# M8357pld.net
KiCad netlist of a schematic drawn in EAGLE
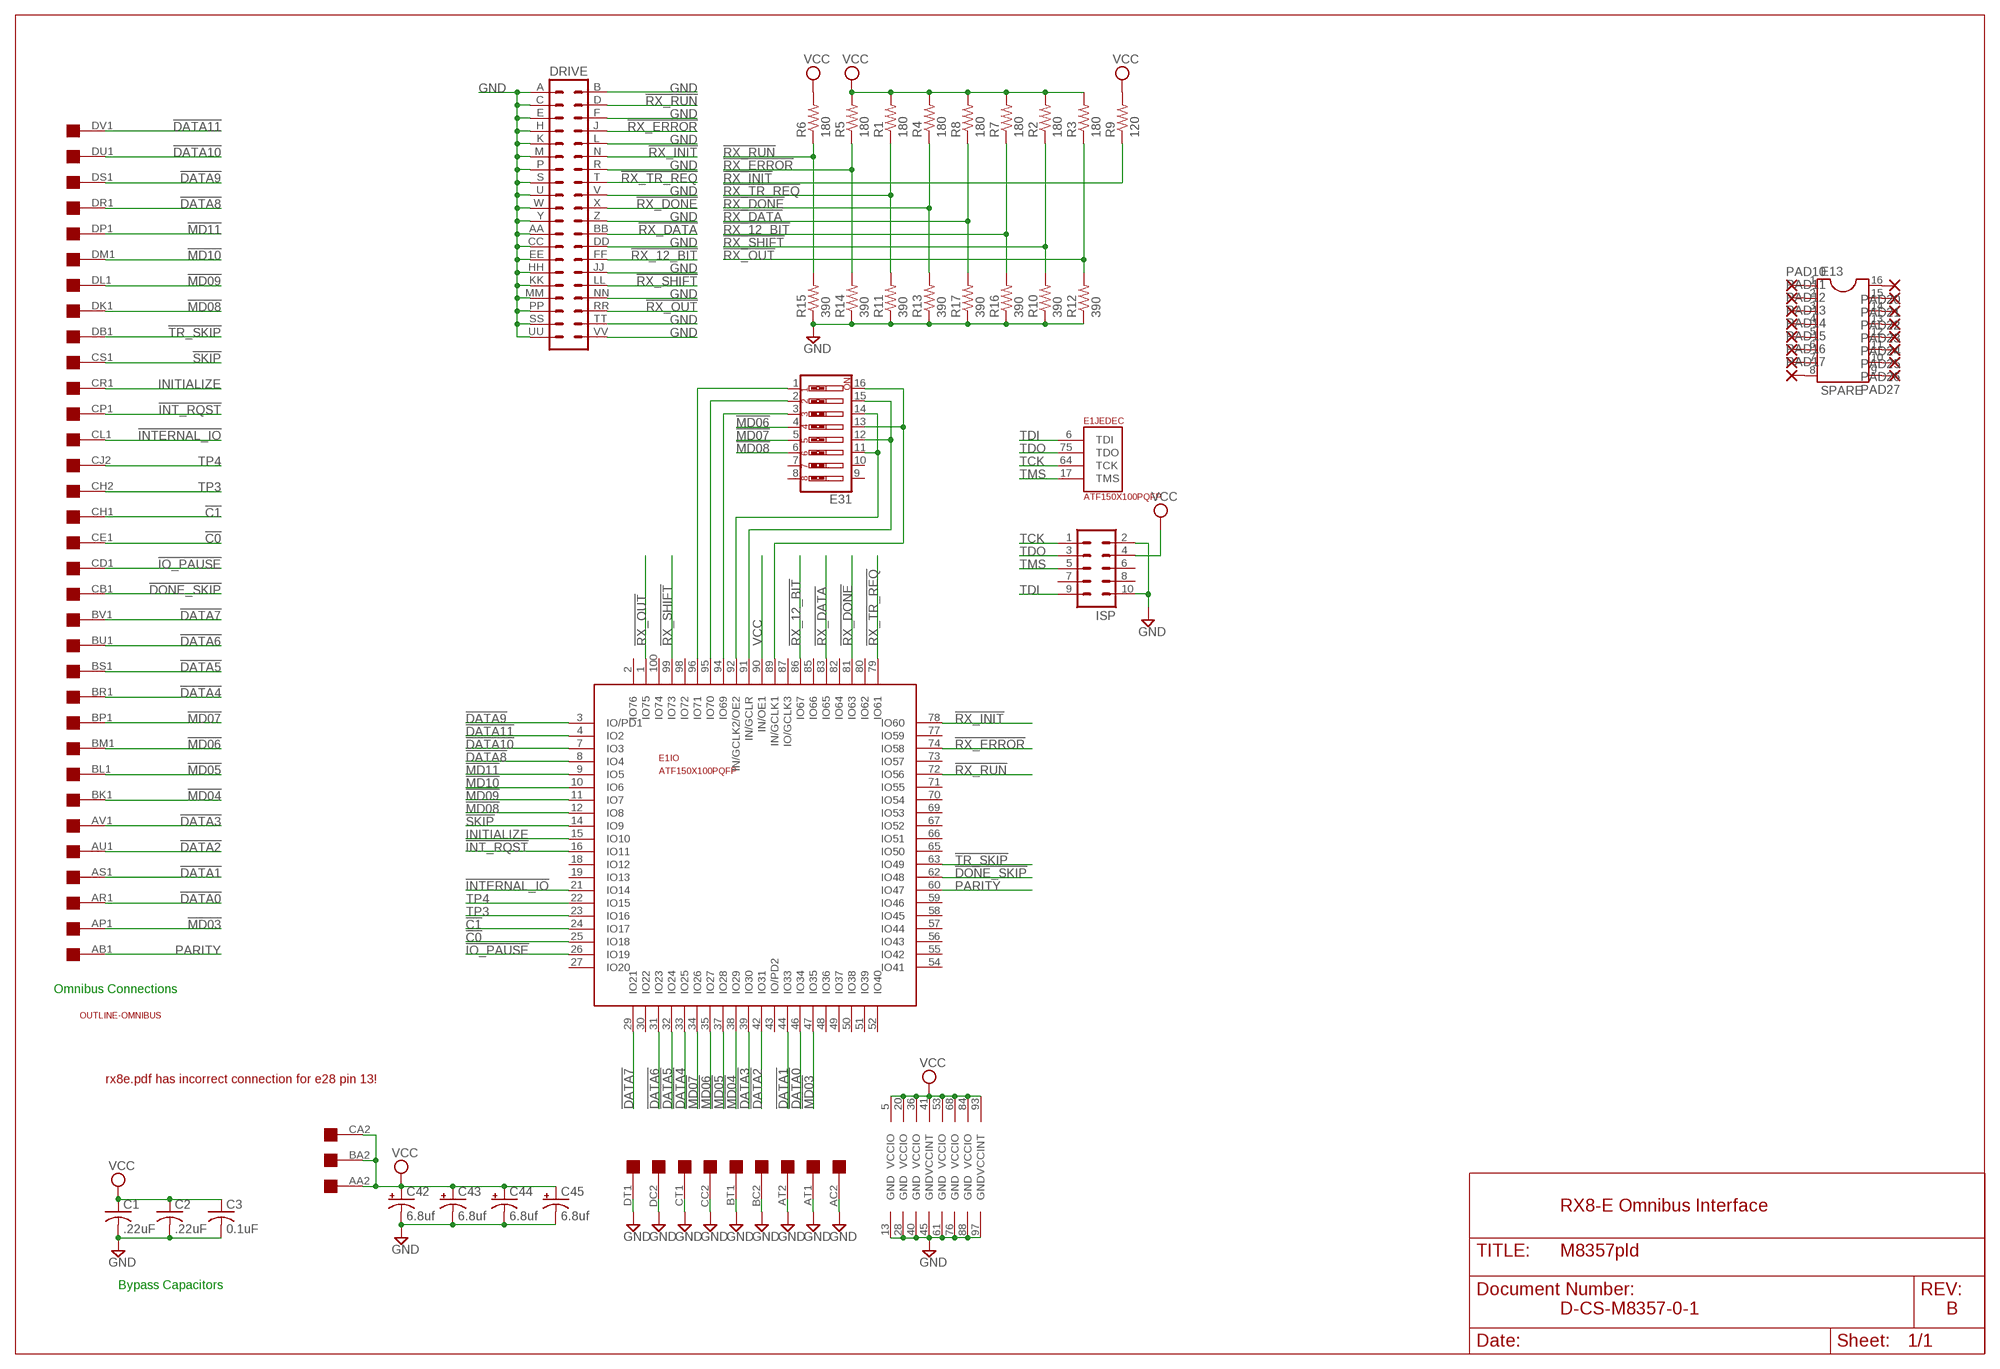
[diagram p0: schematic, sheet 1]

(export (version "E")
  (design (tool "Eeschema 10.0.6"))
  (components
    (comp (ref "C1")
      (value ".22uF")
      (footprint "eagle-import:C050-025X075")
      (libsource (lib "eagle-import") (part "C-US050-025X075"))
    )
    (comp (ref "C2")
      (value ".22uF")
      (footprint "eagle-import:C050-025X075")
      (libsource (lib "eagle-import") (part "C-US050-025X075"))
    )
    (comp (ref "C3")
      (value "0.1uF")
      (footprint "eagle-import:C050-025X075")
      (libsource (lib "eagle-import") (part "C-US050-025X075"))
    )
    (comp (ref "C42")
      (value "6.8uf")
      (footprint "eagle-import:E22-6")
      (libsource (lib "eagle-import") (part "CPOL-USE22-6AXIAL"))
    )
    (comp (ref "C43")
      (value "6.8uf")
      (footprint "eagle-import:E22-6")
      (libsource (lib "eagle-import") (part "CPOL-USE22-6AXIAL"))
    )
    (comp (ref "C44")
      (value "6.8uf")
      (footprint "eagle-import:E22-6")
      (libsource (lib "eagle-import") (part "CPOL-USE22-6AXIAL"))
    )
    (comp (ref "C45")
      (value "6.8uf")
      (footprint "eagle-import:E22-6")
      (libsource (lib "eagle-import") (part "CPOL-USE22-6AXIAL"))
    )
    (comp (ref "DRIVE")
      (value "DEC40PINH")
      (footprint "eagle-import:DEC40PINH")
      (libsource (lib "eagle-import") (part "DEC40PINH"))
    )
    (comp (ref "E1")
      (value "ATF150X100PQFP")
      (footprint "eagle-import:PQFP-100")
      (libsource (lib "eagle-import") (part "ATF150X100PQFP"))
    )
    (comp (ref "E13")
      (value "SPARE")
      (footprint "eagle-import:DIL16")
      (libsource (lib "eagle-import") (part "DIL16"))
    )
    (comp (ref "E31")
      (value "SW_DIP-8")
      (footprint "eagle-import:EDG-08")
      (libsource (lib "eagle-import") (part "SW_DIP-8"))
    )
    (comp (ref "ISP")
      (value "ML10")
      (footprint "eagle-import:ML10")
      (libsource (lib "eagle-import") (part "ML10"))
    )
    (comp (ref "PAD10")
      (value "1,6/0,8")
      (footprint "eagle-import:1,6_0,8")
      (libsource (lib "eagle-import") (part "1,6/0,8"))
    )
    (comp (ref "PAD11")
      (value "1,6/0,8")
      (footprint "eagle-import:1,6_0,8")
      (libsource (lib "eagle-import") (part "1,6/0,8"))
    )
    (comp (ref "PAD12")
      (value "1,6/0,8")
      (footprint "eagle-import:1,6_0,8")
      (libsource (lib "eagle-import") (part "1,6/0,8"))
    )
    (comp (ref "PAD13")
      (value "1,6/0,8")
      (footprint "eagle-import:1,6_0,8")
      (libsource (lib "eagle-import") (part "1,6/0,8"))
    )
    (comp (ref "PAD14")
      (value "1,6/0,8")
      (footprint "eagle-import:1,6_0,8")
      (libsource (lib "eagle-import") (part "1,6/0,8"))
    )
    (comp (ref "PAD15")
      (value "1,6/0,8")
      (footprint "eagle-import:1,6_0,8")
      (libsource (lib "eagle-import") (part "1,6/0,8"))
    )
    (comp (ref "PAD16")
      (value "1,6/0,8")
      (footprint "eagle-import:1,6_0,8")
      (libsource (lib "eagle-import") (part "1,6/0,8"))
    )
    (comp (ref "PAD17")
      (value "1,6/0,8")
      (footprint "eagle-import:1,6_0,8")
      (libsource (lib "eagle-import") (part "1,6/0,8"))
    )
    (comp (ref "PAD20")
      (value "1,6/0,8")
      (footprint "eagle-import:1,6_0,8")
      (libsource (lib "eagle-import") (part "1,6/0,8"))
    )
    (comp (ref "PAD21")
      (value "1,6/0,8")
      (footprint "eagle-import:1,6_0,8")
      (libsource (lib "eagle-import") (part "1,6/0,8"))
    )
    (comp (ref "PAD22")
      (value "1,6/0,8")
      (footprint "eagle-import:1,6_0,8")
      (libsource (lib "eagle-import") (part "1,6/0,8"))
    )
    (comp (ref "PAD23")
      (value "1,6/0,8")
      (footprint "eagle-import:1,6_0,8")
      (libsource (lib "eagle-import") (part "1,6/0,8"))
    )
    (comp (ref "PAD24")
      (value "1,6/0,8")
      (footprint "eagle-import:1,6_0,8")
      (libsource (lib "eagle-import") (part "1,6/0,8"))
    )
    (comp (ref "PAD25")
      (value "1,6/0,8")
      (footprint "eagle-import:1,6_0,8")
      (libsource (lib "eagle-import") (part "1,6/0,8"))
    )
    (comp (ref "PAD26")
      (value "1,6/0,8")
      (footprint "eagle-import:1,6_0,8")
      (libsource (lib "eagle-import") (part "1,6/0,8"))
    )
    (comp (ref "PAD27")
      (value "1,6/0,8")
      (footprint "eagle-import:1,6_0,8")
      (libsource (lib "eagle-import") (part "1,6/0,8"))
    )
    (comp (ref "R1")
      (value "180")
      (footprint "eagle-import:0207_10")
      (libsource (lib "eagle-import") (part "R-US_0207/10"))
    )
    (comp (ref "R2")
      (value "180")
      (footprint "eagle-import:0207_10")
      (libsource (lib "eagle-import") (part "R-US_0207/10"))
    )
    (comp (ref "R3")
      (value "180")
      (footprint "eagle-import:0207_10")
      (libsource (lib "eagle-import") (part "R-US_0207/10"))
    )
    (comp (ref "R4")
      (value "180")
      (footprint "eagle-import:0207_10")
      (libsource (lib "eagle-import") (part "R-US_0207/10"))
    )
    (comp (ref "R5")
      (value "180")
      (footprint "eagle-import:0207_10")
      (libsource (lib "eagle-import") (part "R-US_0207/10"))
    )
    (comp (ref "R6")
      (value "180")
      (footprint "eagle-import:0207_10")
      (libsource (lib "eagle-import") (part "R-US_0207/10"))
    )
    (comp (ref "R7")
      (value "180")
      (footprint "eagle-import:0207_10")
      (libsource (lib "eagle-import") (part "R-US_0207/10"))
    )
    (comp (ref "R8")
      (value "180")
      (footprint "eagle-import:0207_10")
      (libsource (lib "eagle-import") (part "R-US_0207/10"))
    )
    (comp (ref "R9")
      (value "120")
      (footprint "eagle-import:0207_10")
      (libsource (lib "eagle-import") (part "R-US_0207/10"))
    )
    (comp (ref "R10")
      (value "390")
      (footprint "eagle-import:0207_10")
      (libsource (lib "eagle-import") (part "R-US_0207/10"))
    )
    (comp (ref "R11")
      (value "390")
      (footprint "eagle-import:0207_10")
      (libsource (lib "eagle-import") (part "R-US_0207/10"))
    )
    (comp (ref "R12")
      (value "390")
      (footprint "eagle-import:0207_10")
      (libsource (lib "eagle-import") (part "R-US_0207/10"))
    )
    (comp (ref "R13")
      (value "390")
      (footprint "eagle-import:0207_10")
      (libsource (lib "eagle-import") (part "R-US_0207/10"))
    )
    (comp (ref "R14")
      (value "390")
      (footprint "eagle-import:0207_10")
      (libsource (lib "eagle-import") (part "R-US_0207/10"))
    )
    (comp (ref "R15")
      (value "390")
      (footprint "eagle-import:0207_10")
      (libsource (lib "eagle-import") (part "R-US_0207/10"))
    )
    (comp (ref "R16")
      (value "390")
      (footprint "eagle-import:0207_10")
      (libsource (lib "eagle-import") (part "R-US_0207/10"))
    )
    (comp (ref "R17")
      (value "390")
      (footprint "eagle-import:0207_10")
      (libsource (lib "eagle-import") (part "R-US_0207/10"))
    )
    (comp (ref "U$2")
      (value "QUAD")
      (footprint "eagle-import:EDGE-CON8")
      (libsource (lib "eagle-import") (part "QUAD"))
    )
    (comp (ref "U$5")
      (value "OUTLINE-OMNIBUS")
      (footprint "eagle-import:OMNIBUS")
      (libsource (lib "eagle-import") (part "OUTLINE-OMNIBUS"))
    )
  )
  (nets
    (net (code "1") (name "/INITIALIZE") (class "Default")
      (node (ref "E1") (pin "15") (pinfunction "IO10_15") (pintype "bidirectional"))
      (node (ref "U$2") (pin "CR1") (pinfunction "1_CR1") (pintype "bidirectional"))
    )
    (net (code "2") (name "/PARITY") (class "Default")
      (node (ref "E1") (pin "60") (pinfunction "IO47_60") (pintype "bidirectional"))
      (node (ref "U$2") (pin "AB1") (pinfunction "1_AB1") (pintype "bidirectional"))
    )
    (net (code "3") (name "/TCK") (class "Default")
      (node (ref "E1") (pin "64") (pinfunction "TCK_64") (pintype "bidirectional"))
      (node (ref "ISP") (pin "1") (pinfunction "1_1") (pintype "passive"))
    )
    (net (code "4") (name "/TDI") (class "Default")
      (node (ref "E1") (pin "6") (pinfunction "TDI_6") (pintype "bidirectional"))
      (node (ref "ISP") (pin "9") (pinfunction "9_9") (pintype "passive"))
    )
    (net (code "5") (name "/TDO") (class "Default")
      (node (ref "E1") (pin "75") (pinfunction "TDO_75") (pintype "bidirectional"))
      (node (ref "ISP") (pin "3") (pinfunction "3_3") (pintype "passive"))
    )
    (net (code "6") (name "/TMS") (class "Default")
      (node (ref "E1") (pin "17") (pinfunction "TMS_17") (pintype "bidirectional"))
      (node (ref "ISP") (pin "5") (pinfunction "5_5") (pintype "passive"))
    )
    (net (code "7") (name "/TP3") (class "Default")
      (node (ref "E1") (pin "23") (pinfunction "IO16_23") (pintype "bidirectional"))
      (node (ref "U$2") (pin "CH2") (pinfunction "1_CH2") (pintype "bidirectional"))
    )
    (net (code "8") (name "/TP4") (class "Default")
      (node (ref "E1") (pin "22") (pinfunction "IO15_22") (pintype "bidirectional"))
      (node (ref "U$2") (pin "CJ2") (pinfunction "1_CJ2") (pintype "bidirectional"))
    )
    (net (code "9") (name "/~{C0}") (class "Default")
      (node (ref "E1") (pin "25") (pinfunction "IO18_25") (pintype "bidirectional"))
      (node (ref "U$2") (pin "CE1") (pinfunction "1_CE1") (pintype "bidirectional"))
    )
    (net (code "10") (name "/~{C1}") (class "Default")
      (node (ref "E1") (pin "24") (pinfunction "IO17_24") (pintype "bidirectional"))
      (node (ref "U$2") (pin "CH1") (pinfunction "1_CH1") (pintype "bidirectional"))
    )
    (net (code "11") (name "/~{DATA0}") (class "Default")
      (node (ref "E1") (pin "46") (pinfunction "IO34_46") (pintype "bidirectional"))
      (node (ref "U$2") (pin "AR1") (pinfunction "1_AR1") (pintype "bidirectional"))
    )
    (net (code "12") (name "/~{DATA1}") (class "Default")
      (node (ref "E1") (pin "44") (pinfunction "IO33_44") (pintype "bidirectional"))
      (node (ref "U$2") (pin "AS1") (pinfunction "1_AS1") (pintype "bidirectional"))
    )
    (net (code "13") (name "/~{DATA2}") (class "Default")
      (node (ref "E1") (pin "42") (pinfunction "IO31_42") (pintype "bidirectional"))
      (node (ref "U$2") (pin "AU1") (pinfunction "1_AU1") (pintype "bidirectional"))
    )
    (net (code "14") (name "/~{DATA3}") (class "Default")
      (node (ref "E1") (pin "39") (pinfunction "IO30_39") (pintype "bidirectional"))
      (node (ref "U$2") (pin "AV1") (pinfunction "1_AV1") (pintype "bidirectional"))
    )
    (net (code "15") (name "/~{DATA4}") (class "Default")
      (node (ref "E1") (pin "33") (pinfunction "IO25_33") (pintype "bidirectional"))
      (node (ref "U$2") (pin "BR1") (pinfunction "1_BR1") (pintype "bidirectional"))
    )
    (net (code "16") (name "/~{DATA5}") (class "Default")
      (node (ref "E1") (pin "32") (pinfunction "IO24_32") (pintype "bidirectional"))
      (node (ref "U$2") (pin "BS1") (pinfunction "1_BS1") (pintype "bidirectional"))
    )
    (net (code "17") (name "/~{DATA6}") (class "Default")
      (node (ref "E1") (pin "31") (pinfunction "IO23_31") (pintype "bidirectional"))
      (node (ref "U$2") (pin "BU1") (pinfunction "1_BU1") (pintype "bidirectional"))
    )
    (net (code "18") (name "/~{DATA7}") (class "Default")
      (node (ref "E1") (pin "29") (pinfunction "IO21_29") (pintype "bidirectional"))
      (node (ref "U$2") (pin "BV1") (pinfunction "1_BV1") (pintype "bidirectional"))
    )
    (net (code "19") (name "/~{DATA8}") (class "Default")
      (node (ref "E1") (pin "8") (pinfunction "IO4_8") (pintype "bidirectional"))
      (node (ref "U$2") (pin "DR1") (pinfunction "1_DR1") (pintype "bidirectional"))
    )
    (net (code "20") (name "/~{DATA9}") (class "Default")
      (node (ref "E1") (pin "3") (pinfunction "IO/PD1_3") (pintype "bidirectional"))
      (node (ref "U$2") (pin "DS1") (pinfunction "1_DS1") (pintype "bidirectional"))
    )
    (net (code "21") (name "/~{DATA10}") (class "Default")
      (node (ref "E1") (pin "7") (pinfunction "IO3_7") (pintype "bidirectional"))
      (node (ref "U$2") (pin "DU1") (pinfunction "1_DU1") (pintype "bidirectional"))
    )
    (net (code "22") (name "/~{DATA11}") (class "Default")
      (node (ref "E1") (pin "4") (pinfunction "IO2_4") (pintype "bidirectional"))
      (node (ref "U$2") (pin "DV1") (pinfunction "1_DV1") (pintype "bidirectional"))
    )
    (net (code "23") (name "/~{DONE_SKIP}") (class "Default")
      (node (ref "E1") (pin "62") (pinfunction "IO48_62") (pintype "bidirectional"))
      (node (ref "U$2") (pin "CB1") (pinfunction "1_CB1") (pintype "bidirectional"))
    )
    (net (code "24") (name "/~{INTERNAL_IO}") (class "Default")
      (node (ref "E1") (pin "21") (pinfunction "IO14_21") (pintype "bidirectional"))
      (node (ref "U$2") (pin "CL1") (pinfunction "1_CL1") (pintype "bidirectional"))
    )
    (net (code "25") (name "/~{INT_RQST}") (class "Default")
      (node (ref "E1") (pin "16") (pinfunction "IO11_16") (pintype "bidirectional"))
      (node (ref "U$2") (pin "CP1") (pinfunction "1_CP1") (pintype "bidirectional"))
    )
    (net (code "26") (name "/~{IO_PAUSE}") (class "Default")
      (node (ref "E1") (pin "26") (pinfunction "IO19_26") (pintype "bidirectional"))
      (node (ref "U$2") (pin "CD1") (pinfunction "1_CD1") (pintype "bidirectional"))
    )
    (net (code "27") (name "/~{MD03}") (class "Default")
      (node (ref "E1") (pin "47") (pinfunction "IO35_47") (pintype "bidirectional"))
      (node (ref "U$2") (pin "AP1") (pinfunction "1_AP1") (pintype "bidirectional"))
    )
    (net (code "28") (name "/~{MD04}") (class "Default")
      (node (ref "E1") (pin "38") (pinfunction "IO29_38") (pintype "bidirectional"))
      (node (ref "U$2") (pin "BK1") (pinfunction "1_BK1") (pintype "bidirectional"))
    )
    (net (code "29") (name "/~{MD05}") (class "Default")
      (node (ref "E1") (pin "37") (pinfunction "IO28_37") (pintype "bidirectional"))
      (node (ref "U$2") (pin "BL1") (pinfunction "1_BL1") (pintype "bidirectional"))
    )
    (net (code "30") (name "/~{MD06}") (class "Default")
      (node (ref "E1") (pin "35") (pinfunction "IO27_35") (pintype "bidirectional"))
      (node (ref "E31") (pin "4") (pinfunction "4_4") (pintype "passive"))
      (node (ref "U$2") (pin "BM1") (pinfunction "1_BM1") (pintype "bidirectional"))
    )
    (net (code "31") (name "/~{MD07}") (class "Default")
      (node (ref "E1") (pin "34") (pinfunction "IO26_34") (pintype "bidirectional"))
      (node (ref "E31") (pin "5") (pinfunction "5_5") (pintype "passive"))
      (node (ref "U$2") (pin "BP1") (pinfunction "1_BP1") (pintype "bidirectional"))
    )
    (net (code "32") (name "/~{MD08}") (class "Default")
      (node (ref "E1") (pin "12") (pinfunction "IO8_12") (pintype "bidirectional"))
      (node (ref "E31") (pin "6") (pinfunction "6_6") (pintype "passive"))
      (node (ref "U$2") (pin "DK1") (pinfunction "1_DK1") (pintype "bidirectional"))
    )
    (net (code "33") (name "/~{MD09}") (class "Default")
      (node (ref "E1") (pin "11") (pinfunction "IO7_11") (pintype "bidirectional"))
      (node (ref "U$2") (pin "DL1") (pinfunction "1_DL1") (pintype "bidirectional"))
    )
    (net (code "34") (name "/~{MD10}") (class "Default")
      (node (ref "E1") (pin "10") (pinfunction "IO6_10") (pintype "bidirectional"))
      (node (ref "U$2") (pin "DM1") (pinfunction "1_DM1") (pintype "bidirectional"))
    )
    (net (code "35") (name "/~{MD11}") (class "Default")
      (node (ref "E1") (pin "9") (pinfunction "IO5_9") (pintype "bidirectional"))
      (node (ref "U$2") (pin "DP1") (pinfunction "1_DP1") (pintype "bidirectional"))
    )
    (net (code "36") (name "/~{RX_12_BIT}") (class "Default")
      (node (ref "DRIVE") (pin "FF") (pinfunction "28_FF") (pintype "bidirectional"))
      (node (ref "E1") (pin "86") (pinfunction "IO67_86") (pintype "bidirectional"))
      (node (ref "R16") (pin "2") (pinfunction "2_2") (pintype "passive"))
      (node (ref "R7") (pin "1") (pinfunction "1_1") (pintype "passive"))
    )
    (net (code "37") (name "/~{RX_DATA}") (class "Default")
      (node (ref "DRIVE") (pin "BB") (pinfunction "24_BB") (pintype "bidirectional"))
      (node (ref "E1") (pin "83") (pinfunction "IO65_83") (pintype "bidirectional"))
      (node (ref "R17") (pin "2") (pinfunction "2_2") (pintype "passive"))
      (node (ref "R8") (pin "1") (pinfunction "1_1") (pintype "passive"))
    )
    (net (code "38") (name "/~{RX_DONE}") (class "Default")
      (node (ref "DRIVE") (pin "X") (pinfunction "20_X") (pintype "bidirectional"))
      (node (ref "E1") (pin "81") (pinfunction "IO63_81") (pintype "bidirectional"))
      (node (ref "R13") (pin "2") (pinfunction "2_2") (pintype "passive"))
      (node (ref "R4") (pin "1") (pinfunction "1_1") (pintype "passive"))
    )
    (net (code "39") (name "/~{RX_ERROR}") (class "Default")
      (node (ref "DRIVE") (pin "J") (pinfunction "8_J") (pintype "bidirectional"))
      (node (ref "E1") (pin "74") (pinfunction "IO58_74") (pintype "bidirectional"))
      (node (ref "R14") (pin "2") (pinfunction "2_2") (pintype "passive"))
      (node (ref "R5") (pin "1") (pinfunction "1_1") (pintype "passive"))
    )
    (net (code "40") (name "/~{RX_INIT}") (class "Default")
      (node (ref "DRIVE") (pin "N") (pinfunction "12_N") (pintype "bidirectional"))
      (node (ref "E1") (pin "78") (pinfunction "IO60_78") (pintype "bidirectional"))
      (node (ref "R9") (pin "1") (pinfunction "1_1") (pintype "passive"))
    )
    (net (code "41") (name "/~{RX_OUT}") (class "Default")
      (node (ref "DRIVE") (pin "RR") (pinfunction "36_RR") (pintype "bidirectional"))
      (node (ref "E1") (pin "1") (pinfunction "IO75_1") (pintype "bidirectional"))
      (node (ref "R12") (pin "2") (pinfunction "2_2") (pintype "passive"))
      (node (ref "R3") (pin "1") (pinfunction "1_1") (pintype "passive"))
    )
    (net (code "42") (name "/~{RX_RUN}") (class "Default")
      (node (ref "DRIVE") (pin "D") (pinfunction "4_D") (pintype "bidirectional"))
      (node (ref "E1") (pin "72") (pinfunction "IO56_72") (pintype "bidirectional"))
      (node (ref "R15") (pin "2") (pinfunction "2_2") (pintype "passive"))
      (node (ref "R6") (pin "1") (pinfunction "1_1") (pintype "passive"))
    )
    (net (code "43") (name "/~{RX_SHIFT}") (class "Default")
      (node (ref "DRIVE") (pin "LL") (pinfunction "32_LL") (pintype "bidirectional"))
      (node (ref "E1") (pin "99") (pinfunction "IO73_99") (pintype "bidirectional"))
      (node (ref "R10") (pin "2") (pinfunction "2_2") (pintype "passive"))
      (node (ref "R2") (pin "1") (pinfunction "1_1") (pintype "passive"))
    )
    (net (code "44") (name "/~{RX_TR_REQ}") (class "Default")
      (node (ref "DRIVE") (pin "T") (pinfunction "16_T") (pintype "bidirectional"))
      (node (ref "E1") (pin "79") (pinfunction "IO61_79") (pintype "bidirectional"))
      (node (ref "R1") (pin "1") (pinfunction "1_1") (pintype "passive"))
      (node (ref "R11") (pin "2") (pinfunction "2_2") (pintype "passive"))
    )
    (net (code "45") (name "/~{SKIP}") (class "Default")
      (node (ref "E1") (pin "14") (pinfunction "IO9_14") (pintype "bidirectional"))
      (node (ref "U$2") (pin "CS1") (pinfunction "1_CS1") (pintype "bidirectional"))
    )
    (net (code "46") (name "/~{TR_SKIP}") (class "Default")
      (node (ref "E1") (pin "63") (pinfunction "IO49_63") (pintype "bidirectional"))
      (node (ref "U$2") (pin "DB1") (pinfunction "1_DB1") (pintype "bidirectional"))
    )
    (net (code "47") (name "GND") (class "Default")
      (node (ref "C1") (pin "2") (pinfunction "2_2") (pintype "passive"))
      (node (ref "C2") (pin "2") (pinfunction "2_2") (pintype "passive"))
      (node (ref "C3") (pin "2") (pinfunction "2_2") (pintype "passive"))
      (node (ref "C42") (pin "-") (pinfunction "-_-") (pintype "passive"))
      (node (ref "C43") (pin "-") (pinfunction "-_-") (pintype "passive"))
      (node (ref "C44") (pin "-") (pinfunction "-_-") (pintype "passive"))
      (node (ref "C45") (pin "-") (pinfunction "-_-") (pintype "passive"))
      (node (ref "DRIVE") (pin "A") (pinfunction "1_A") (pintype "bidirectional"))
      (node (ref "DRIVE") (pin "AA") (pinfunction "23_AA") (pintype "bidirectional"))
      (node (ref "DRIVE") (pin "B") (pinfunction "2_B") (pintype "bidirectional"))
      (node (ref "DRIVE") (pin "C") (pinfunction "3_C") (pintype "bidirectional"))
      (node (ref "DRIVE") (pin "CC") (pinfunction "25_CC") (pintype "bidirectional"))
      (node (ref "DRIVE") (pin "DD") (pinfunction "26_DD") (pintype "bidirectional"))
      (node (ref "DRIVE") (pin "E") (pinfunction "5_E") (pintype "bidirectional"))
      (node (ref "DRIVE") (pin "EE") (pinfunction "27_EE") (pintype "bidirectional"))
      (node (ref "DRIVE") (pin "F") (pinfunction "6_F") (pintype "bidirectional"))
      (node (ref "DRIVE") (pin "H") (pinfunction "7_H") (pintype "bidirectional"))
      (node (ref "DRIVE") (pin "HH") (pinfunction "29_HH") (pintype "bidirectional"))
      (node (ref "DRIVE") (pin "JJ") (pinfunction "30_JJ") (pintype "bidirectional"))
      (node (ref "DRIVE") (pin "K") (pinfunction "9_K") (pintype "bidirectional"))
      (node (ref "DRIVE") (pin "KK") (pinfunction "31_KK") (pintype "bidirectional"))
      (node (ref "DRIVE") (pin "L") (pinfunction "10_L") (pintype "bidirectional"))
      (node (ref "DRIVE") (pin "M") (pinfunction "11_M") (pintype "bidirectional"))
      (node (ref "DRIVE") (pin "MM") (pinfunction "33_MM") (pintype "bidirectional"))
      (node (ref "DRIVE") (pin "NN") (pinfunction "34_NN") (pintype "bidirectional"))
      (node (ref "DRIVE") (pin "P") (pinfunction "13_P") (pintype "bidirectional"))
      (node (ref "DRIVE") (pin "PP") (pinfunction "35_PP") (pintype "bidirectional"))
      (node (ref "DRIVE") (pin "R") (pinfunction "14_R") (pintype "bidirectional"))
      (node (ref "DRIVE") (pin "S") (pinfunction "15_S") (pintype "bidirectional"))
      (node (ref "DRIVE") (pin "SS") (pinfunction "37_SS") (pintype "bidirectional"))
      (node (ref "DRIVE") (pin "TT") (pinfunction "38_TT") (pintype "bidirectional"))
      (node (ref "DRIVE") (pin "U") (pinfunction "17_U") (pintype "bidirectional"))
      (node (ref "DRIVE") (pin "UU") (pinfunction "39_UU") (pintype "bidirectional"))
      (node (ref "DRIVE") (pin "V") (pinfunction "18_V") (pintype "bidirectional"))
      (node (ref "DRIVE") (pin "VV") (pinfunction "40_VV") (pintype "bidirectional"))
      (node (ref "DRIVE") (pin "W") (pinfunction "19_W") (pintype "bidirectional"))
      (node (ref "DRIVE") (pin "Y") (pinfunction "21_Y") (pintype "bidirectional"))
      (node (ref "DRIVE") (pin "Z") (pinfunction "22_Z") (pintype "bidirectional"))
      (node (ref "E1") (pin "13") (pinfunction "GND_13") (pintype "power_in"))
      (node (ref "E1") (pin "28") (pinfunction "GND_28") (pintype "power_in"))
      (node (ref "E1") (pin "40") (pinfunction "GND_40") (pintype "power_in"))
      (node (ref "E1") (pin "45") (pinfunction "GND_45") (pintype "power_in"))
      (node (ref "E1") (pin "61") (pinfunction "GND_61") (pintype "power_in"))
      (node (ref "E1") (pin "76") (pinfunction "GND_76") (pintype "power_in"))
      (node (ref "E1") (pin "88") (pinfunction "GND_88") (pintype "power_in"))
      (node (ref "E1") (pin "97") (pinfunction "GND_97") (pintype "power_in"))
      (node (ref "ISP") (pin "10") (pinfunction "10_10") (pintype "passive"))
      (node (ref "ISP") (pin "2") (pinfunction "2_2") (pintype "passive"))
      (node (ref "R10") (pin "1") (pinfunction "1_1") (pintype "passive"))
      (node (ref "R11") (pin "1") (pinfunction "1_1") (pintype "passive"))
      (node (ref "R12") (pin "1") (pinfunction "1_1") (pintype "passive"))
      (node (ref "R13") (pin "1") (pinfunction "1_1") (pintype "passive"))
      (node (ref "R14") (pin "1") (pinfunction "1_1") (pintype "passive"))
      (node (ref "R15") (pin "1") (pinfunction "1_1") (pintype "passive"))
      (node (ref "R16") (pin "1") (pinfunction "1_1") (pintype "passive"))
      (node (ref "R17") (pin "1") (pinfunction "1_1") (pintype "passive"))
      (node (ref "U$2") (pin "AC2") (pinfunction "1_AC2") (pintype "bidirectional"))
      (node (ref "U$2") (pin "AT1") (pinfunction "1_AT1") (pintype "bidirectional"))
      (node (ref "U$2") (pin "AT2") (pinfunction "1_AT2") (pintype "bidirectional"))
      (node (ref "U$2") (pin "BC2") (pinfunction "1_BC2") (pintype "bidirectional"))
      (node (ref "U$2") (pin "BT1") (pinfunction "1_BT1") (pintype "bidirectional"))
      (node (ref "U$2") (pin "CC2") (pinfunction "1_CC2") (pintype "bidirectional"))
      (node (ref "U$2") (pin "CT1") (pinfunction "1_CT1") (pintype "bidirectional"))
      (node (ref "U$2") (pin "DC2") (pinfunction "1_DC2") (pintype "bidirectional"))
      (node (ref "U$2") (pin "DT1") (pinfunction "1_DT1") (pintype "bidirectional"))
    )
    (net (code "48") (name "Net-(E1Q-IN{slash}GCLK1)") (class "Default")
      (node (ref "E1") (pin "89") (pinfunction "IN/GCLK1_89") (pintype "input"))
      (node (ref "E31") (pin "13") (pinfunction "13_13") (pintype "passive"))
      (node (ref "E31") (pin "16") (pinfunction "16_16") (pintype "passive"))
    )
    (net (code "49") (name "Net-(E1Q-IN{slash}GCLK2{slash}OE2)") (class "Default")
      (node (ref "E1") (pin "92") (pinfunction "IN/GCLK2/OE2_92") (pintype "input"))
      (node (ref "E31") (pin "11") (pinfunction "11_11") (pintype "passive"))
      (node (ref "E31") (pin "14") (pinfunction "14_14") (pintype "passive"))
    )
    (net (code "50") (name "Net-(E1Q-IN{slash}GCLR)") (class "Default")
      (node (ref "E1") (pin "91") (pinfunction "IN/GCLR_91") (pintype "input"))
      (node (ref "E31") (pin "12") (pinfunction "12_12") (pintype "passive"))
      (node (ref "E31") (pin "15") (pinfunction "15_15") (pintype "passive"))
    )
    (net (code "51") (name "Net-(E1Q-IO69)") (class "Default")
      (node (ref "E1") (pin "94") (pinfunction "IO69_94") (pintype "bidirectional"))
      (node (ref "E31") (pin "3") (pinfunction "3_3") (pintype "passive"))
    )
    (net (code "52") (name "Net-(E1Q-IO70)") (class "Default")
      (node (ref "E1") (pin "95") (pinfunction "IO70_95") (pintype "bidirectional"))
      (node (ref "E31") (pin "2") (pinfunction "2_2") (pintype "passive"))
    )
    (net (code "53") (name "Net-(E1Q-IO71)") (class "Default")
      (node (ref "E1") (pin "96") (pinfunction "IO71_96") (pintype "bidirectional"))
      (node (ref "E31") (pin "1") (pinfunction "1_1") (pintype "passive"))
    )
    (net (code "54") (name "Net-(PAD10-P)") (class "Default")
      (node (ref "E13") (pin "1") (pinfunction "1_1") (pintype "passive"))
      (node (ref "PAD10") (pin "1") (pinfunction "P_1") (pintype "passive"))
    )
    (net (code "55") (name "Net-(PAD11-P)") (class "Default")
      (node (ref "E13") (pin "2") (pinfunction "2_2") (pintype "passive"))
      (node (ref "PAD11") (pin "1") (pinfunction "P_1") (pintype "passive"))
    )
    (net (code "56") (name "Net-(PAD12-P)") (class "Default")
      (node (ref "E13") (pin "3") (pinfunction "3_3") (pintype "passive"))
      (node (ref "PAD12") (pin "1") (pinfunction "P_1") (pintype "passive"))
    )
    (net (code "57") (name "Net-(PAD13-P)") (class "Default")
      (node (ref "E13") (pin "4") (pinfunction "4_4") (pintype "passive"))
      (node (ref "PAD13") (pin "1") (pinfunction "P_1") (pintype "passive"))
    )
    (net (code "58") (name "Net-(PAD14-P)") (class "Default")
      (node (ref "E13") (pin "5") (pinfunction "5_5") (pintype "passive"))
      (node (ref "PAD14") (pin "1") (pinfunction "P_1") (pintype "passive"))
    )
    (net (code "59") (name "Net-(PAD15-P)") (class "Default")
      (node (ref "E13") (pin "6") (pinfunction "6_6") (pintype "passive"))
      (node (ref "PAD15") (pin "1") (pinfunction "P_1") (pintype "passive"))
    )
    (net (code "60") (name "Net-(PAD16-P)") (class "Default")
      (node (ref "E13") (pin "7") (pinfunction "7_7") (pintype "passive"))
      (node (ref "PAD16") (pin "1") (pinfunction "P_1") (pintype "passive"))
    )
    (net (code "61") (name "Net-(PAD17-P)") (class "Default")
      (node (ref "E13") (pin "8") (pinfunction "8_8") (pintype "passive"))
      (node (ref "PAD17") (pin "1") (pinfunction "P_1") (pintype "passive"))
    )
    (net (code "62") (name "Net-(PAD20-P)") (class "Default")
      (node (ref "E13") (pin "16") (pinfunction "16_16") (pintype "passive"))
      (node (ref "PAD20") (pin "1") (pinfunction "P_1") (pintype "passive"))
    )
    (net (code "63") (name "Net-(PAD21-P)") (class "Default")
      (node (ref "E13") (pin "15") (pinfunction "15_15") (pintype "passive"))
      (node (ref "PAD21") (pin "1") (pinfunction "P_1") (pintype "passive"))
    )
    (net (code "64") (name "Net-(PAD22-P)") (class "Default")
      (node (ref "E13") (pin "14") (pinfunction "14_14") (pintype "passive"))
      (node (ref "PAD22") (pin "1") (pinfunction "P_1") (pintype "passive"))
    )
    (net (code "65") (name "Net-(PAD23-P)") (class "Default")
      (node (ref "E13") (pin "13") (pinfunction "13_13") (pintype "passive"))
      (node (ref "PAD23") (pin "1") (pinfunction "P_1") (pintype "passive"))
    )
    (net (code "66") (name "Net-(PAD24-P)") (class "Default")
      (node (ref "E13") (pin "12") (pinfunction "12_12") (pintype "passive"))
      (node (ref "PAD24") (pin "1") (pinfunction "P_1") (pintype "passive"))
    )
    (net (code "67") (name "Net-(PAD25-P)") (class "Default")
      (node (ref "E13") (pin "11") (pinfunction "11_11") (pintype "passive"))
      (node (ref "PAD25") (pin "1") (pinfunction "P_1") (pintype "passive"))
    )
    (net (code "68") (name "Net-(PAD26-P)") (class "Default")
      (node (ref "E13") (pin "10") (pinfunction "10_10") (pintype "passive"))
      (node (ref "PAD26") (pin "1") (pinfunction "P_1") (pintype "passive"))
    )
    (net (code "69") (name "Net-(PAD27-P)") (class "Default")
      (node (ref "E13") (pin "9") (pinfunction "9_9") (pintype "passive"))
      (node (ref "PAD27") (pin "1") (pinfunction "P_1") (pintype "passive"))
    )
    (net (code "70") (name "VCC") (class "Default")
      (node (ref "C1") (pin "1") (pinfunction "1_1") (pintype "passive"))
      (node (ref "C2") (pin "1") (pinfunction "1_1") (pintype "passive"))
      (node (ref "C3") (pin "1") (pinfunction "1_1") (pintype "passive"))
      (node (ref "C42") (pin "+") (pinfunction "+_+") (pintype "passive"))
      (node (ref "C43") (pin "+") (pinfunction "+_+") (pintype "passive"))
      (node (ref "C44") (pin "+") (pinfunction "+_+") (pintype "passive"))
      (node (ref "C45") (pin "+") (pinfunction "+_+") (pintype "passive"))
      (node (ref "E1") (pin "20") (pinfunction "VCCIO_20") (pintype "power_in"))
      (node (ref "E1") (pin "36") (pinfunction "VCCIO_36") (pintype "power_in"))
      (node (ref "E1") (pin "41") (pinfunction "VCCINT_41") (pintype "power_in"))
      (node (ref "E1") (pin "5") (pinfunction "VCCIO_5") (pintype "power_in"))
      (node (ref "E1") (pin "53") (pinfunction "VCCIO_53") (pintype "power_in"))
      (node (ref "E1") (pin "68") (pinfunction "VCCIO_68") (pintype "power_in"))
      (node (ref "E1") (pin "84") (pinfunction "VCCIO_84") (pintype "power_in"))
      (node (ref "E1") (pin "90") (pinfunction "IN/OE1_90") (pintype "input"))
      (node (ref "E1") (pin "93") (pinfunction "VCCINT_93") (pintype "power_in"))
      (node (ref "ISP") (pin "4") (pinfunction "4_4") (pintype "passive"))
      (node (ref "R1") (pin "2") (pinfunction "2_2") (pintype "passive"))
      (node (ref "R2") (pin "2") (pinfunction "2_2") (pintype "passive"))
      (node (ref "R3") (pin "2") (pinfunction "2_2") (pintype "passive"))
      (node (ref "R4") (pin "2") (pinfunction "2_2") (pintype "passive"))
      (node (ref "R5") (pin "2") (pinfunction "2_2") (pintype "passive"))
      (node (ref "R6") (pin "2") (pinfunction "2_2") (pintype "passive"))
      (node (ref "R7") (pin "2") (pinfunction "2_2") (pintype "passive"))
      (node (ref "R8") (pin "2") (pinfunction "2_2") (pintype "passive"))
      (node (ref "R9") (pin "2") (pinfunction "2_2") (pintype "passive"))
      (node (ref "U$2") (pin "AA2") (pinfunction "1_AA2") (pintype "bidirectional"))
      (node (ref "U$2") (pin "BA2") (pinfunction "1_BA2") (pintype "bidirectional"))
      (node (ref "U$2") (pin "CA2") (pinfunction "1_CA2") (pintype "bidirectional"))
    )
    (net (code "71") (name "unconnected-(E1Q-IO12-Pad18)") (class "Default")
      (node (ref "E1") (pin "18") (pinfunction "IO12_18") (pintype "bidirectional"))
    )
    (net (code "72") (name "unconnected-(E1Q-IO13-Pad19)") (class "Default")
      (node (ref "E1") (pin "19") (pinfunction "IO13_19") (pintype "bidirectional"))
    )
    (net (code "73") (name "unconnected-(E1Q-IO20-Pad27)") (class "Default")
      (node (ref "E1") (pin "27") (pinfunction "IO20_27") (pintype "bidirectional"))
    )
    (net (code "74") (name "unconnected-(E1Q-IO22-Pad30)") (class "Default")
      (node (ref "E1") (pin "30") (pinfunction "IO22_30") (pintype "bidirectional"))
    )
    (net (code "75") (name "unconnected-(E1Q-IO36-Pad48)") (class "Default")
      (node (ref "E1") (pin "48") (pinfunction "IO36_48") (pintype "bidirectional"))
    )
    (net (code "76") (name "unconnected-(E1Q-IO37-Pad49)") (class "Default")
      (node (ref "E1") (pin "49") (pinfunction "IO37_49") (pintype "bidirectional"))
    )
    (net (code "77") (name "unconnected-(E1Q-IO38-Pad50)") (class "Default")
      (node (ref "E1") (pin "50") (pinfunction "IO38_50") (pintype "bidirectional"))
    )
    (net (code "78") (name "unconnected-(E1Q-IO39-Pad51)") (class "Default")
      (node (ref "E1") (pin "51") (pinfunction "IO39_51") (pintype "bidirectional"))
    )
    (net (code "79") (name "unconnected-(E1Q-IO40-Pad52)") (class "Default")
      (node (ref "E1") (pin "52") (pinfunction "IO40_52") (pintype "bidirectional"))
    )
    (net (code "80") (name "unconnected-(E1Q-IO41-Pad54)") (class "Default")
      (node (ref "E1") (pin "54") (pinfunction "IO41_54") (pintype "bidirectional"))
    )
    (net (code "81") (name "unconnected-(E1Q-IO42-Pad55)") (class "Default")
      (node (ref "E1") (pin "55") (pinfunction "IO42_55") (pintype "bidirectional"))
    )
    (net (code "82") (name "unconnected-(E1Q-IO43-Pad56)") (class "Default")
      (node (ref "E1") (pin "56") (pinfunction "IO43_56") (pintype "bidirectional"))
    )
    (net (code "83") (name "unconnected-(E1Q-IO44-Pad57)") (class "Default")
      (node (ref "E1") (pin "57") (pinfunction "IO44_57") (pintype "bidirectional"))
    )
    (net (code "84") (name "unconnected-(E1Q-IO45-Pad58)") (class "Default")
      (node (ref "E1") (pin "58") (pinfunction "IO45_58") (pintype "bidirectional"))
    )
    (net (code "85") (name "unconnected-(E1Q-IO46-Pad59)") (class "Default")
      (node (ref "E1") (pin "59") (pinfunction "IO46_59") (pintype "bidirectional"))
    )
    (net (code "86") (name "unconnected-(E1Q-IO50-Pad65)") (class "Default")
      (node (ref "E1") (pin "65") (pinfunction "IO50_65") (pintype "bidirectional"))
    )
    (net (code "87") (name "unconnected-(E1Q-IO51-Pad66)") (class "Default")
      (node (ref "E1") (pin "66") (pinfunction "IO51_66") (pintype "bidirectional"))
    )
    (net (code "88") (name "unconnected-(E1Q-IO52-Pad67)") (class "Default")
      (node (ref "E1") (pin "67") (pinfunction "IO52_67") (pintype "bidirectional"))
    )
    (net (code "89") (name "unconnected-(E1Q-IO53-Pad69)") (class "Default")
      (node (ref "E1") (pin "69") (pinfunction "IO53_69") (pintype "bidirectional"))
    )
    (net (code "90") (name "unconnected-(E1Q-IO54-Pad70)") (class "Default")
      (node (ref "E1") (pin "70") (pinfunction "IO54_70") (pintype "bidirectional"))
    )
    (net (code "91") (name "unconnected-(E1Q-IO55-Pad71)") (class "Default")
      (node (ref "E1") (pin "71") (pinfunction "IO55_71") (pintype "bidirectional"))
    )
    (net (code "92") (name "unconnected-(E1Q-IO57-Pad73)") (class "Default")
      (node (ref "E1") (pin "73") (pinfunction "IO57_73") (pintype "bidirectional"))
    )
    (net (code "93") (name "unconnected-(E1Q-IO59-Pad77)") (class "Default")
      (node (ref "E1") (pin "77") (pinfunction "IO59_77") (pintype "bidirectional"))
    )
    (net (code "94") (name "unconnected-(E1Q-IO62-Pad80)") (class "Default")
      (node (ref "E1") (pin "80") (pinfunction "IO62_80") (pintype "bidirectional"))
    )
    (net (code "95") (name "unconnected-(E1Q-IO64-Pad82)") (class "Default")
      (node (ref "E1") (pin "82") (pinfunction "IO64_82") (pintype "bidirectional"))
    )
    (net (code "96") (name "unconnected-(E1Q-IO66-Pad85)") (class "Default")
      (node (ref "E1") (pin "85") (pinfunction "IO66_85") (pintype "bidirectional"))
    )
    (net (code "97") (name "unconnected-(E1Q-IO72-Pad98)") (class "Default")
      (node (ref "E1") (pin "98") (pinfunction "IO72_98") (pintype "bidirectional"))
    )
    (net (code "98") (name "unconnected-(E1Q-IO74-Pad100)") (class "Default")
      (node (ref "E1") (pin "100") (pinfunction "IO74_100") (pintype "bidirectional"))
    )
    (net (code "99") (name "unconnected-(E1Q-IO76-Pad2)") (class "Default")
      (node (ref "E1") (pin "2") (pinfunction "IO76_2") (pintype "bidirectional"))
    )
    (net (code "100") (name "unconnected-(E1Q-IO{slash}GCLK3-Pad87)") (class "Default")
      (node (ref "E1") (pin "87") (pinfunction "IO/GCLK3_87") (pintype "bidirectional"))
    )
    (net (code "101") (name "unconnected-(E1Q-IO{slash}PD2-Pad43)") (class "Default")
      (node (ref "E1") (pin "43") (pinfunction "IO/PD2_43") (pintype "bidirectional"))
    )
    (net (code "102") (name "unconnected-(E31-Pad7)") (class "Default")
      (node (ref "E31") (pin "7") (pinfunction "7_7") (pintype "passive"))
    )
    (net (code "103") (name "unconnected-(E31-Pad8)") (class "Default")
      (node (ref "E31") (pin "8") (pinfunction "8_8") (pintype "passive"))
    )
    (net (code "104") (name "unconnected-(E31-Pad9)") (class "Default")
      (node (ref "E31") (pin "9") (pinfunction "9_9") (pintype "passive"))
    )
    (net (code "105") (name "unconnected-(E31-Pad10)") (class "Default")
      (node (ref "E31") (pin "10") (pinfunction "10_10") (pintype "passive"))
    )
    (net (code "106") (name "unconnected-(ISP-Pad6)") (class "Default")
      (node (ref "ISP") (pin "6") (pinfunction "6_6") (pintype "passive"))
    )
    (net (code "107") (name "unconnected-(ISP-Pad7)") (class "Default")
      (node (ref "ISP") (pin "7") (pinfunction "7_7") (pintype "passive"))
    )
    (net (code "108") (name "unconnected-(ISP-Pad8)") (class "Default")
      (node (ref "ISP") (pin "8") (pinfunction "8_8") (pintype "passive"))
    )
  )
)
